# PowerSupply.net
KiCad netlist of a schematic drawn in Altium Designer
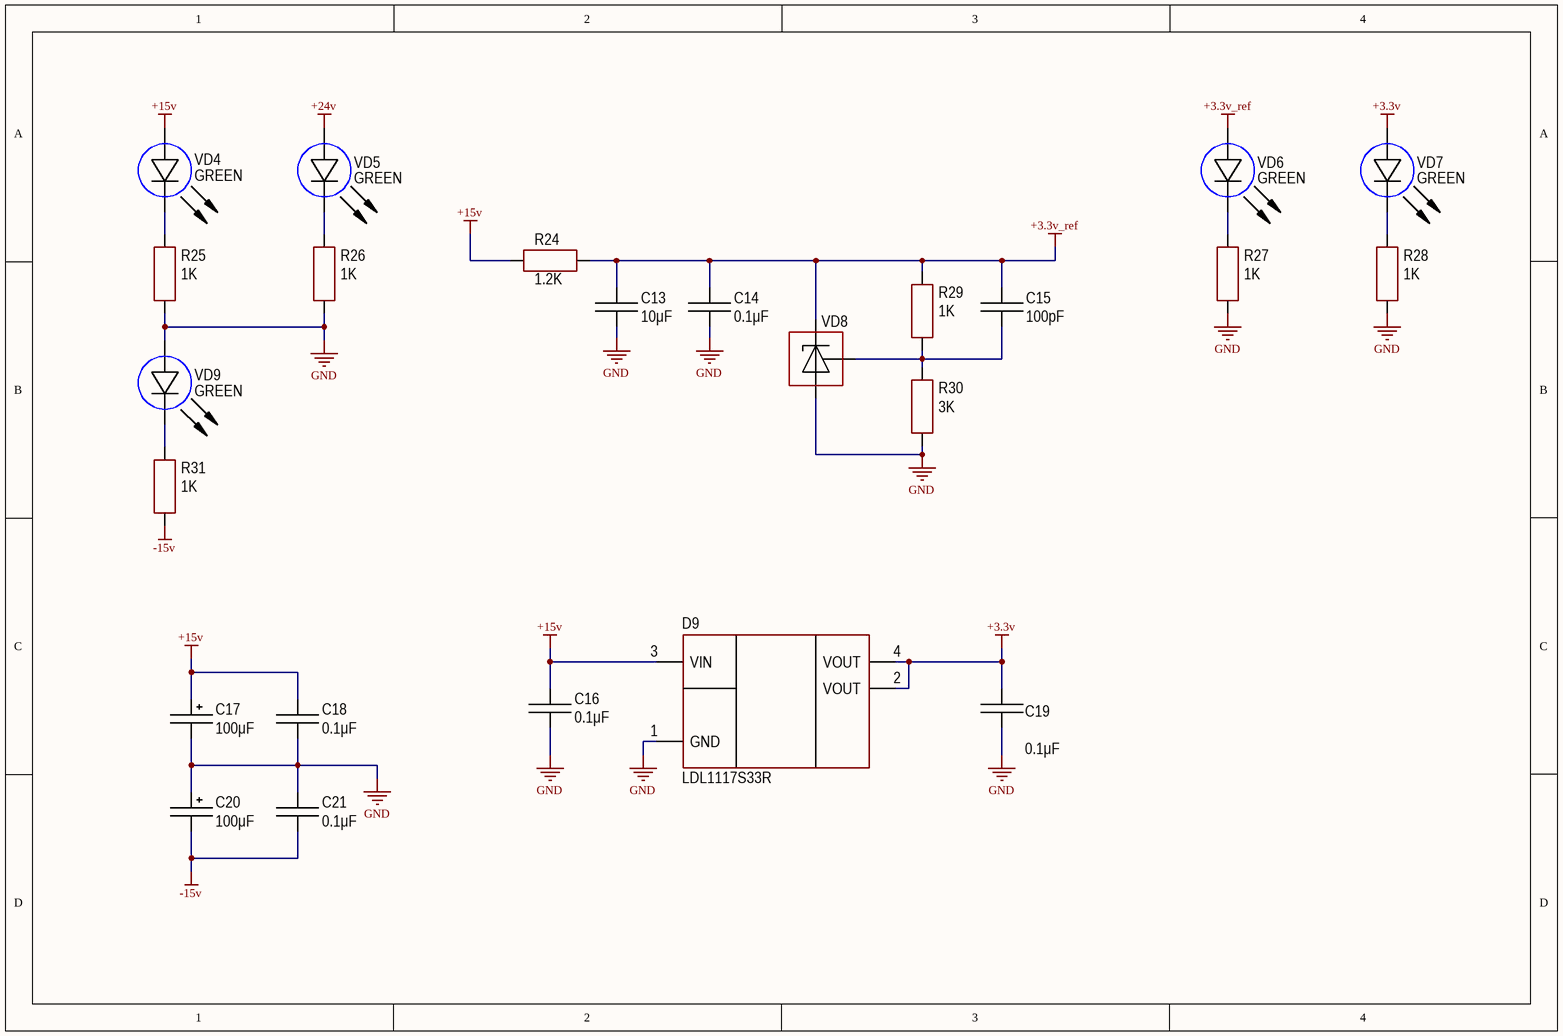
[diagram p0: PowerSupply.SchDoc]

(export (version "E")
  (design (tool "Eeschema 10.0.6"))
  (components
    (comp (ref "C13")
      (value "10μF")
      (footprint "StandardCase:CAP: 1206")
      (fields
        (field (name "MANUFACTURER") "Yageo")
        (field (name "PARTNUMBER") "CC1206KRX7R9BB104")
        (field (name "VALUEMANUFACTURERPARTNUMBER") "Ceramic capacitor, 10μF, X7R, ±10%, 50V, 1206, -55...+125°C")
      )
      (libsource (lib "Capacitor") (part "Ceramic_1206"))
    )
    (comp (ref "C14")
      (value "0.1μF")
      (footprint "StandardCase:CAP: 1206")
      (fields
        (field (name "MANUFACTURER") "Yageo")
        (field (name "PARTNUMBER") "CC1206KRX7R9BB104")
        (field (name "VALUEMANUFACTURERPARTNUMBER") "Ceramic capacitor, 0.1μF, X7R, ±10%, 50V, 1206, -55...+125°C")
      )
      (libsource (lib "Capacitor") (part "Ceramic_1206"))
    )
    (comp (ref "C15")
      (value "100pF")
      (footprint "StandardCase:CAP: 1206")
      (fields
        (field (name "MANUFACTURER") "Yageo")
        (field (name "PARTNUMBER") "CC1206KRX7R9BB104")
        (field (name "VALUEMANUFACTURERPARTNUMBER") "Ceramic capacitor, 100pF, X7R, ±10%, 50V, 1206, -55...+125°C")
      )
      (libsource (lib "Capacitor") (part "Ceramic_1206"))
    )
    (comp (ref "C16")
      (value "0.1μF")
      (footprint "StandardCase:CAP: 1206")
      (fields
        (field (name "MANUFACTURER") "Yageo")
        (field (name "PARTNUMBER") "CC1206KRX7R9BB104")
        (field (name "VALUEMANUFACTURERPARTNUMBER") "Ceramic capacitor, 0.1μF, X7R, ±10%, 50V, 1206, -55...+125°C")
      )
      (libsource (lib "Capacitor") (part "Ceramic_1206"))
    )
    (comp (ref "C17")
      (value "100μF")
      (footprint "PcbLib1:CAPAE7466X80L")
      (fields
        (field (name "MANUFACTURER") "Wurth")
        (field (name "PARTNUMBER") "EEEFK1V101XP")
        (field (name "VALUEMANUFACTURERPARTNUMBER") "EEEFK1V101XP, 100μF, 35V, D8")
      )
      (libsource (lib "Capacitor") (part "Aluminium"))
    )
    (comp (ref "C18")
      (value "0.1μF")
      (footprint "StandardCase:CAP: 1206")
      (fields
        (field (name "MANUFACTURER") "Yageo")
        (field (name "PARTNUMBER") "CC1206KRX7R9BB104")
        (field (name "VALUEMANUFACTURERPARTNUMBER") "Ceramic capacitor, 0.1μF, X7R, ±10%, 50V, 1206, -55...+125°C")
      )
      (libsource (lib "Capacitor") (part "Ceramic_1206"))
    )
    (comp (ref "C19")
      (value "0.1μF")
      (footprint "StandardCase:CAP: 1206")
      (fields
        (field (name "MANUFACTURER") "Yageo")
        (field (name "PARTNUMBER") "CC1206KRX7R9BB104")
        (field (name "VALUEMANUFACTURERPARTNUMBER") "Ceramic capacitor, 0.1μF, X7R, ±10%, 50V, 1206, -55...+125°C")
      )
      (libsource (lib "Capacitor") (part "Ceramic_1206"))
    )
    (comp (ref "C20")
      (value "100μF")
      (footprint "PcbLib1:CAPAE7466X80L")
      (fields
        (field (name "MANUFACTURER") "Wurth")
        (field (name "PARTNUMBER") "EEEFK1V101XP")
        (field (name "VALUEMANUFACTURERPARTNUMBER") "EEEFK1V101XP, 100μF, 35V, D8")
      )
      (libsource (lib "Capacitor") (part "Aluminium"))
    )
    (comp (ref "C21")
      (value "0.1μF")
      (footprint "StandardCase:CAP: 1206")
      (fields
        (field (name "MANUFACTURER") "Yageo")
        (field (name "PARTNUMBER") "CC1206KRX7R9BB104")
        (field (name "VALUEMANUFACTURERPARTNUMBER") "Ceramic capacitor, 0.1μF, X7R, ±10%, 50V, 1206, -55...+125°C")
      )
      (libsource (lib "Capacitor") (part "Ceramic_1206"))
    )
    (comp (ref "D9")
      (value "~")
      (footprint "StandardCase:SOT223")
      (description "Linear voltage regulator")
      (fields
        (field (name "MANUFACTURER") "STMicroelectronics")
        (field (name "VALUEMANUFACTURERPARTNUMBER") "Linear voltage regulator, input 3.9...18V, 0.6V, output 3.3V, 1.2A, -40...+85°C, SOT223")
        (field (name "PARTNUMBER") "LDL1117S33R")
      )
      (libsource (lib "IC. Power supply") (part "LDL1117S33R"))
    )
    (comp (ref "R24")
      (value "1.2K")
      (footprint "StandardCase:RES: 1206")
      (fields
        (field (name "MANUFACTURER") "Yageo")
        (field (name "PARTNUMBER") "RC1206JR-07100RL")
        (field (name "VALUEMANUFACTURERPARTNUMBER") "Resistor film, 1.2K, ±5%, 1206, 0.25W, -55...+125°C")
      )
      (libsource (lib "") (part "Resistor_1206_2"))
    )
    (comp (ref "R25")
      (value "1K")
      (footprint "StandardCase:RES: 1206")
      (fields
        (field (name "MANUFACTURER") "Yageo")
        (field (name "PARTNUMBER") "RC1206JR-07100RL")
        (field (name "VALUEMANUFACTURERPARTNUMBER") "Resistor film, 1K, ±5%, 1206, 0.25W, -55...+125°C")
      )
      (libsource (lib "Resistor") (part "Resistor_1206"))
    )
    (comp (ref "R26")
      (value "1K")
      (footprint "StandardCase:RES: 1206")
      (fields
        (field (name "MANUFACTURER") "Yageo")
        (field (name "PARTNUMBER") "RC1206JR-07100RL")
        (field (name "VALUEMANUFACTURERPARTNUMBER") "Resistor film, 1K, ±5%, 1206, 0.25W, -55...+125°C")
      )
      (libsource (lib "Resistor") (part "Resistor_1206"))
    )
    (comp (ref "R27")
      (value "1K")
      (footprint "StandardCase:RES: 1206")
      (fields
        (field (name "MANUFACTURER") "Yageo")
        (field (name "PARTNUMBER") "RC1206JR-07100RL")
        (field (name "VALUEMANUFACTURERPARTNUMBER") "Resistor film, 1K, ±5%, 1206, 0.25W, -55...+125°C")
      )
      (libsource (lib "Resistor") (part "Resistor_1206"))
    )
    (comp (ref "R28")
      (value "1K")
      (footprint "StandardCase:RES: 1206")
      (fields
        (field (name "MANUFACTURER") "Yageo")
        (field (name "PARTNUMBER") "RC1206JR-07100RL")
        (field (name "VALUEMANUFACTURERPARTNUMBER") "Resistor film, 1K, ±5%, 1206, 0.25W, -55...+125°C")
      )
      (libsource (lib "Resistor") (part "Resistor_1206"))
    )
    (comp (ref "R29")
      (value "1K")
      (footprint "StandardCase:RES: 1206")
      (fields
        (field (name "MANUFACTURER") "Yageo")
        (field (name "PARTNUMBER") "RC1206JR-07100RL")
        (field (name "VALUEMANUFACTURERPARTNUMBER") "Resistor film, 1K, ±5%, 1206, 0.25W, -55...+125°C")
      )
      (libsource (lib "Resistor") (part "Resistor_1206"))
    )
    (comp (ref "R30")
      (value "3K")
      (footprint "StandardCase:RES: 1206")
      (fields
        (field (name "MANUFACTURER") "Yageo")
        (field (name "PARTNUMBER") "RC1206JR-07100RL")
        (field (name "VALUEMANUFACTURERPARTNUMBER") "Resistor film, 3K, ±5%, 1206, 0.25W, -55...+125°C")
      )
      (libsource (lib "Resistor") (part "Resistor_1206"))
    )
    (comp (ref "R31")
      (value "1K")
      (footprint "StandardCase:RES: 1206")
      (fields
        (field (name "MANUFACTURER") "Yageo")
        (field (name "PARTNUMBER") "RC1206JR-07100RL")
        (field (name "VALUEMANUFACTURERPARTNUMBER") "Resistor film, 1K, ±5%, 1206, 0.25W, -55...+125°C")
      )
      (libsource (lib "") (part "Resistor_1206_1"))
    )
    (comp (ref "VD4")
      (value "~")
      (footprint "StandardCase:LED: 1206G")
      (fields
        (field (name "VALUEMANUFACTURERPARTNUMBER") "LED, Green, *, *, *, -55...+150°C")
        (field (name "COLOR") "GREEN")
      )
      (libsource (lib "Diode") (part "LED_single"))
    )
    (comp (ref "VD5")
      (value "~")
      (footprint "StandardCase:LED: 1206G")
      (fields
        (field (name "VALUEMANUFACTURERPARTNUMBER") "LED, Green, *, *, *, -55...+150°C")
        (field (name "COLOR") "GREEN")
      )
      (libsource (lib "Diode") (part "LED_single"))
    )
    (comp (ref "VD6")
      (value "~")
      (footprint "StandardCase:LED: 1206G")
      (fields
        (field (name "VALUEMANUFACTURERPARTNUMBER") "LED, Green, *, *, *, -55...+150°C")
        (field (name "COLOR") "GREEN")
      )
      (libsource (lib "Diode") (part "LED_single"))
    )
    (comp (ref "VD7")
      (value "~")
      (footprint "StandardCase:LED: 1206G")
      (fields
        (field (name "VALUEMANUFACTURERPARTNUMBER") "LED, Green, *, *, *, -55...+150°C")
        (field (name "COLOR") "GREEN")
      )
      (libsource (lib "Diode") (part "LED_single"))
    )
    (comp (ref "VD8")
      (value "~")
      (footprint "StandardCase:SOT23")
      (fields
        (field (name "MANUFACTURER") "Texas Instruments")
        (field (name "VALUEMANUFACTURERPARTNUMBER") "Program zener diode, 36V, 100mA, 2.495V, ±1%, SOT-23, 0...+70°C")
        (field (name "TOLERANCE") "±1%")
      )
      (libsource (lib "Diode") (part "Zener_program"))
    )
    (comp (ref "VD9")
      (value "~")
      (footprint "StandardCase:LED: 1206G")
      (fields
        (field (name "VALUEMANUFACTURERPARTNUMBER") "LED, Green, *, *, *, -55...+150°C")
        (field (name "COLOR") "GREEN")
      )
      (libsource (lib "Diode") (part "LED_single"))
    )
  )
  (nets
    (net (code "1") (name "+3.3v") (class "Default")
      (node (ref "C19") (pin "2") (pinfunction "2_2") (pintype "power_in"))
      (node (ref "D9") (pin "2") (pinfunction "VOUT_2") (pintype "power_in"))
      (node (ref "D9") (pin "4") (pinfunction "VOUT_4") (pintype "power_in"))
      (node (ref "VD7") (pin "1") (pinfunction "A_1") (pintype "passive"))
    )
    (net (code "2") (name "+3.3v_ref") (class "Default")
      (node (ref "C13") (pin "1") (pinfunction "1_1") (pintype "power_in"))
      (node (ref "C14") (pin "1") (pinfunction "1_1") (pintype "power_in"))
      (node (ref "C15") (pin "1") (pinfunction "1_1") (pintype "power_in"))
      (node (ref "R24") (pin "1") (pinfunction "1_1") (pintype "passive"))
      (node (ref "R29") (pin "2") (pinfunction "2_2") (pintype "passive"))
      (node (ref "VD6") (pin "1") (pinfunction "A_1") (pintype "passive"))
      (node (ref "VD8") (pin "1") (pinfunction "1_1") (pintype "passive"))
    )
    (net (code "3") (name "+15v") (class "Default")
      (node (ref "C16") (pin "2") (pinfunction "2_2") (pintype "power_in"))
      (node (ref "C17") (pin "1") (pinfunction "1_1") (pintype "power_in"))
      (node (ref "C18") (pin "2") (pinfunction "2_2") (pintype "power_in"))
      (node (ref "D9") (pin "3") (pinfunction "VIN_3") (pintype "power_in"))
      (node (ref "R24") (pin "2") (pinfunction "2_2") (pintype "passive"))
      (node (ref "VD4") (pin "1") (pinfunction "A_1") (pintype "passive"))
    )
    (net (code "4") (name "+24v") (class "Default")
      (node (ref "VD5") (pin "1") (pinfunction "A_1") (pintype "passive"))
    )
    (net (code "5") (name "-15v") (class "Default")
      (node (ref "C20") (pin "2") (pinfunction "2_2") (pintype "power_in"))
      (node (ref "C21") (pin "1") (pinfunction "1_1") (pintype "power_in"))
      (node (ref "R31") (pin "2") (pinfunction "2_2") (pintype "passive"))
    )
    (net (code "6") (name "GND") (class "Default")
      (node (ref "C13") (pin "2") (pinfunction "2_2") (pintype "power_in"))
      (node (ref "C14") (pin "2") (pinfunction "2_2") (pintype "power_in"))
      (node (ref "C16") (pin "1") (pinfunction "1_1") (pintype "power_in"))
      (node (ref "C17") (pin "2") (pinfunction "2_2") (pintype "power_in"))
      (node (ref "C18") (pin "1") (pinfunction "1_1") (pintype "power_in"))
      (node (ref "C19") (pin "1") (pinfunction "1_1") (pintype "power_in"))
      (node (ref "C20") (pin "1") (pinfunction "1_1") (pintype "power_in"))
      (node (ref "C21") (pin "2") (pinfunction "2_2") (pintype "power_in"))
      (node (ref "D9") (pin "1") (pinfunction "GND_1") (pintype "power_in"))
      (node (ref "R25") (pin "1") (pinfunction "1_1") (pintype "passive"))
      (node (ref "R26") (pin "1") (pinfunction "1_1") (pintype "passive"))
      (node (ref "R27") (pin "1") (pinfunction "1_1") (pintype "passive"))
      (node (ref "R28") (pin "1") (pinfunction "1_1") (pintype "passive"))
      (node (ref "R30") (pin "1") (pinfunction "1_1") (pintype "passive"))
      (node (ref "VD8") (pin "3") (pinfunction "3_3") (pintype "passive"))
      (node (ref "VD9") (pin "1") (pinfunction "A_1") (pintype "passive"))
    )
    (net (code "7") (name "Net-(C15-Pad2)") (class "Default")
      (node (ref "C15") (pin "2") (pinfunction "2_2") (pintype "power_in"))
      (node (ref "R29") (pin "1") (pinfunction "1_1") (pintype "passive"))
      (node (ref "R30") (pin "2") (pinfunction "2_2") (pintype "passive"))
      (node (ref "VD8") (pin "2") (pinfunction "2_2") (pintype "passive"))
    )
    (net (code "8") (name "Net-(VD4-C)") (class "Default")
      (node (ref "R25") (pin "2") (pinfunction "2_2") (pintype "passive"))
      (node (ref "VD4") (pin "2") (pinfunction "C_2") (pintype "passive"))
    )
    (net (code "9") (name "Net-(VD5-C)") (class "Default")
      (node (ref "R26") (pin "2") (pinfunction "2_2") (pintype "passive"))
      (node (ref "VD5") (pin "2") (pinfunction "C_2") (pintype "passive"))
    )
    (net (code "10") (name "Net-(VD6-C)") (class "Default")
      (node (ref "R27") (pin "2") (pinfunction "2_2") (pintype "passive"))
      (node (ref "VD6") (pin "2") (pinfunction "C_2") (pintype "passive"))
    )
    (net (code "11") (name "Net-(VD7-C)") (class "Default")
      (node (ref "R28") (pin "2") (pinfunction "2_2") (pintype "passive"))
      (node (ref "VD7") (pin "2") (pinfunction "C_2") (pintype "passive"))
    )
    (net (code "12") (name "Net-(VD9-C)") (class "Default")
      (node (ref "R31") (pin "1") (pinfunction "1_1") (pintype "passive"))
      (node (ref "VD9") (pin "2") (pinfunction "C_2") (pintype "passive"))
    )
  )
)
